# spider_mx8_2side.net
KiCad netlist of a schematic drawn in EAGLE
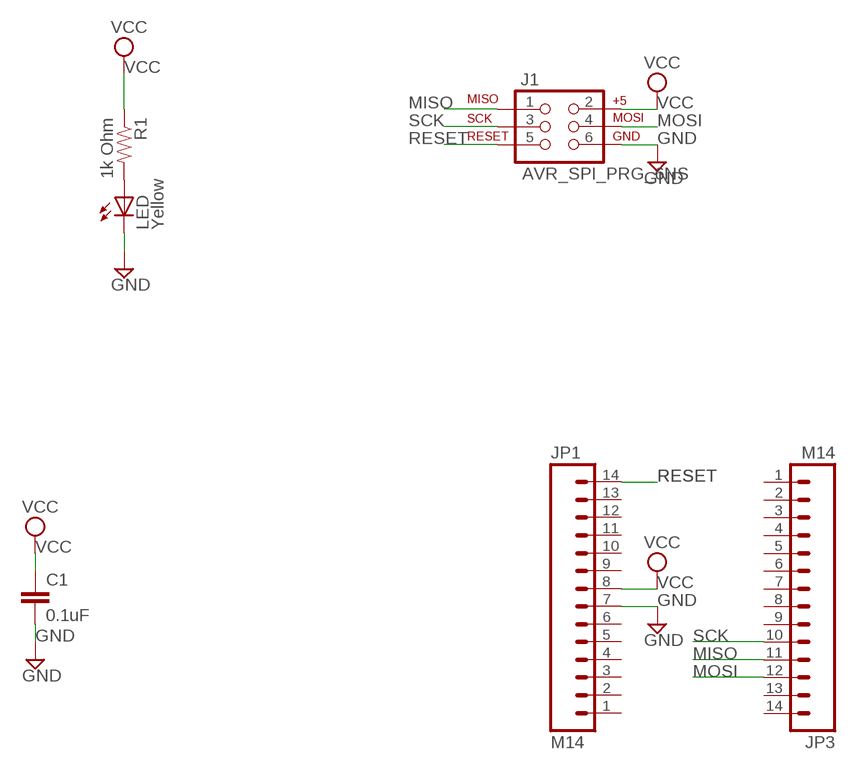
[diagram p0: schematic, sheet 1]

(export (version "E")
  (design (tool "Eeschema 10.0.6"))
  (components
    (comp (ref "C1")
      (value "0.1uF")
      (footprint "eagle-import:1206")
      (libsource (lib "eagle-import") (part "CAP1206"))
    )
    (comp (ref "J1")
      (value "AVR_SPI_PRG_6NS")
      (footprint "eagle-import:2X3-NS")
      (libsource (lib "eagle-import") (part "AVR_SPI_PRG_6NS"))
    )
    (comp (ref "JP1")
      (value "M14")
      (footprint "eagle-import:1X14")
      (libsource (lib "eagle-import") (part "M14"))
    )
    (comp (ref "JP3")
      (value "M14")
      (footprint "eagle-import:1X14")
      (libsource (lib "eagle-import") (part "M14"))
    )
    (comp (ref "LED")
      (value "Yellow")
      (footprint "eagle-import:LED-1206")
      (libsource (lib "eagle-import") (part "LED-YELLOWLILYPAD"))
    )
    (comp (ref "R1")
      (value "1k Ohm")
      (footprint "eagle-import:1206")
      (libsource (lib "eagle-import") (part "RESISTOR1206"))
    )
  )
  (nets
    (net (code "1") (name "/MISO") (class "Default")
      (node (ref "J1") (pin "1") (pinfunction "1_1") (pintype "passive"))
      (node (ref "JP3") (pin "11") (pinfunction "11_11") (pintype "passive"))
    )
    (net (code "2") (name "/MOSI") (class "Default")
      (node (ref "J1") (pin "4") (pinfunction "4_4") (pintype "passive"))
      (node (ref "JP3") (pin "12") (pinfunction "12_12") (pintype "passive"))
    )
    (net (code "3") (name "/RESET") (class "Default")
      (node (ref "J1") (pin "5") (pinfunction "5_5") (pintype "passive"))
      (node (ref "JP1") (pin "14") (pinfunction "14_14") (pintype "passive"))
    )
    (net (code "4") (name "/SCK") (class "Default")
      (node (ref "J1") (pin "3") (pinfunction "3_3") (pintype "passive"))
      (node (ref "JP3") (pin "10") (pinfunction "10_10") (pintype "passive"))
    )
    (net (code "5") (name "GND") (class "Default")
      (node (ref "C1") (pin "2") (pinfunction "2_2") (pintype "passive"))
      (node (ref "J1") (pin "6") (pinfunction "6_6") (pintype "passive"))
      (node (ref "JP1") (pin "7") (pinfunction "7_7") (pintype "passive"))
      (node (ref "LED") (pin "C") (pinfunction "C_C") (pintype "passive"))
    )
    (net (code "6") (name "Net-(LED-PadA)") (class "Default")
      (node (ref "LED") (pin "A") (pinfunction "A_A") (pintype "passive"))
      (node (ref "R1") (pin "2") (pinfunction "2_2") (pintype "passive"))
    )
    (net (code "7") (name "VCC") (class "Default")
      (node (ref "C1") (pin "1") (pinfunction "1_1") (pintype "passive"))
      (node (ref "J1") (pin "2") (pinfunction "2_2") (pintype "passive"))
      (node (ref "JP1") (pin "8") (pinfunction "8_8") (pintype "passive"))
      (node (ref "R1") (pin "1") (pinfunction "1_1") (pintype "passive"))
    )
    (net (code "8") (name "unconnected-(JP1-Pad1)") (class "Default")
      (node (ref "JP1") (pin "1") (pinfunction "1_1") (pintype "passive"))
    )
    (net (code "9") (name "unconnected-(JP1-Pad2)") (class "Default")
      (node (ref "JP1") (pin "2") (pinfunction "2_2") (pintype "passive"))
    )
    (net (code "10") (name "unconnected-(JP1-Pad3)") (class "Default")
      (node (ref "JP1") (pin "3") (pinfunction "3_3") (pintype "passive"))
    )
    (net (code "11") (name "unconnected-(JP1-Pad4)") (class "Default")
      (node (ref "JP1") (pin "4") (pinfunction "4_4") (pintype "passive"))
    )
    (net (code "12") (name "unconnected-(JP1-Pad5)") (class "Default")
      (node (ref "JP1") (pin "5") (pinfunction "5_5") (pintype "passive"))
    )
    (net (code "13") (name "unconnected-(JP1-Pad6)") (class "Default")
      (node (ref "JP1") (pin "6") (pinfunction "6_6") (pintype "passive"))
    )
    (net (code "14") (name "unconnected-(JP1-Pad9)") (class "Default")
      (node (ref "JP1") (pin "9") (pinfunction "9_9") (pintype "passive"))
    )
    (net (code "15") (name "unconnected-(JP1-Pad10)") (class "Default")
      (node (ref "JP1") (pin "10") (pinfunction "10_10") (pintype "passive"))
    )
    (net (code "16") (name "unconnected-(JP1-Pad11)") (class "Default")
      (node (ref "JP1") (pin "11") (pinfunction "11_11") (pintype "passive"))
    )
    (net (code "17") (name "unconnected-(JP1-Pad12)") (class "Default")
      (node (ref "JP1") (pin "12") (pinfunction "12_12") (pintype "passive"))
    )
    (net (code "18") (name "unconnected-(JP1-Pad13)") (class "Default")
      (node (ref "JP1") (pin "13") (pinfunction "13_13") (pintype "passive"))
    )
    (net (code "19") (name "unconnected-(JP3-Pad1)") (class "Default")
      (node (ref "JP3") (pin "1") (pinfunction "1_1") (pintype "passive"))
    )
    (net (code "20") (name "unconnected-(JP3-Pad2)") (class "Default")
      (node (ref "JP3") (pin "2") (pinfunction "2_2") (pintype "passive"))
    )
    (net (code "21") (name "unconnected-(JP3-Pad3)") (class "Default")
      (node (ref "JP3") (pin "3") (pinfunction "3_3") (pintype "passive"))
    )
    (net (code "22") (name "unconnected-(JP3-Pad4)") (class "Default")
      (node (ref "JP3") (pin "4") (pinfunction "4_4") (pintype "passive"))
    )
    (net (code "23") (name "unconnected-(JP3-Pad5)") (class "Default")
      (node (ref "JP3") (pin "5") (pinfunction "5_5") (pintype "passive"))
    )
    (net (code "24") (name "unconnected-(JP3-Pad6)") (class "Default")
      (node (ref "JP3") (pin "6") (pinfunction "6_6") (pintype "passive"))
    )
    (net (code "25") (name "unconnected-(JP3-Pad7)") (class "Default")
      (node (ref "JP3") (pin "7") (pinfunction "7_7") (pintype "passive"))
    )
    (net (code "26") (name "unconnected-(JP3-Pad8)") (class "Default")
      (node (ref "JP3") (pin "8") (pinfunction "8_8") (pintype "passive"))
    )
    (net (code "27") (name "unconnected-(JP3-Pad9)") (class "Default")
      (node (ref "JP3") (pin "9") (pinfunction "9_9") (pintype "passive"))
    )
    (net (code "28") (name "unconnected-(JP3-Pad13)") (class "Default")
      (node (ref "JP3") (pin "13") (pinfunction "13_13") (pintype "passive"))
    )
    (net (code "29") (name "unconnected-(JP3-Pad14)") (class "Default")
      (node (ref "JP3") (pin "14") (pinfunction "14_14") (pintype "passive"))
    )
  )
)
